# Schematic1_0.net
KiCad netlist of a schematic drawn in EAGLE
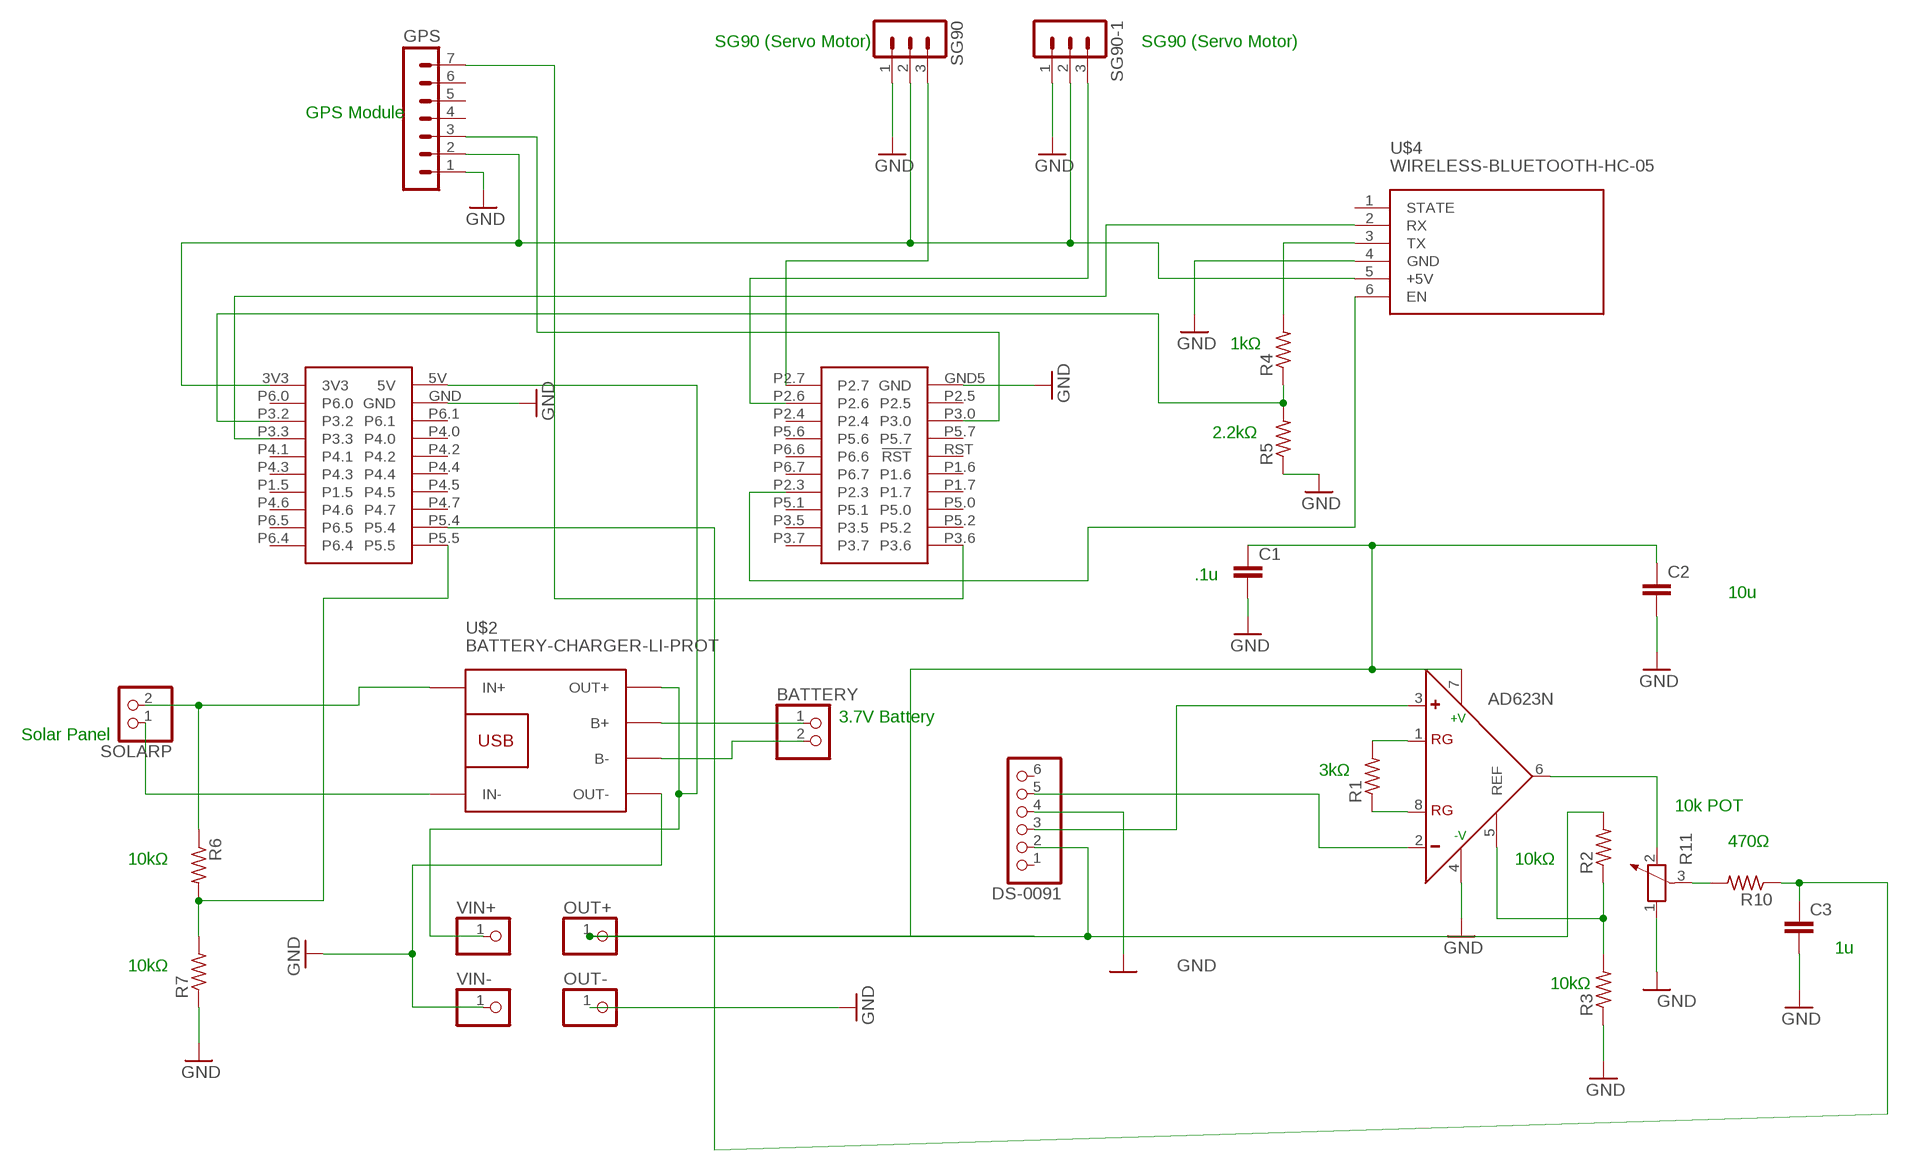
[diagram p0: schematic, sheet 1]

(export (version "E")
  (design (tool "Eeschema 10.0.6"))
  (components
    (comp (ref "BATTERY")
      (value "PINHD-1X2")
      (footprint "eagle-import:1X02")
      (libsource (lib "eagle-import") (part "PINHD-1X2"))
    )
    (comp (ref "C1")
      (value "C2,5-3")
      (footprint "eagle-import:C2.5-3")
      (libsource (lib "eagle-import") (part "C2,5-3"))
    )
    (comp (ref "C2")
      (value "C2,5-3")
      (footprint "eagle-import:C2.5-3")
      (libsource (lib "eagle-import") (part "C2,5-3"))
    )
    (comp (ref "C3")
      (value "C2,5-3")
      (footprint "eagle-import:C2.5-3")
      (libsource (lib "eagle-import") (part "C2,5-3"))
    )
    (comp (ref "DS-0091")
      (value "PINHD-1X6")
      (footprint "eagle-import:1X06")
      (libsource (lib "eagle-import") (part "PINHD-1X6"))
    )
    (comp (ref "GPS")
      (value "MA07-1")
      (footprint "eagle-import:MA07-1")
      (libsource (lib "eagle-import") (part "MA07-1"))
    )
    (comp (ref "IC1")
      (value "AD623N")
      (footprint "eagle-import:DIL08")
      (fields (field (name "MF") "ALTERA CORPORATION") (field (name "MPN") "AD623ANZ"))
      (libsource (lib "eagle-import") (part "AD623N"))
    )
    (comp (ref "OUT+")
      (value "PINHD-1X1")
      (footprint "eagle-import:1X01")
      (libsource (lib "eagle-import") (part "PINHD-1X1"))
    )
    (comp (ref "OUT-")
      (value "PINHD-1X1")
      (footprint "eagle-import:1X01")
      (libsource (lib "eagle-import") (part "PINHD-1X1"))
    )
    (comp (ref "R1")
      (value "R-US_0204/7")
      (footprint "eagle-import:0204_7")
      (libsource (lib "eagle-import") (part "R-US_0204/7"))
    )
    (comp (ref "R2")
      (value "R-US_0204/7")
      (footprint "eagle-import:0204_7")
      (libsource (lib "eagle-import") (part "R-US_0204/7"))
    )
    (comp (ref "R3")
      (value "R-US_0204/7")
      (footprint "eagle-import:0204_7")
      (libsource (lib "eagle-import") (part "R-US_0204/7"))
    )
    (comp (ref "R4")
      (value "R-US_0204/7")
      (footprint "eagle-import:0204_7")
      (libsource (lib "eagle-import") (part "R-US_0204/7"))
    )
    (comp (ref "R5")
      (value "R-US_0204/7")
      (footprint "eagle-import:0204_7")
      (libsource (lib "eagle-import") (part "R-US_0204/7"))
    )
    (comp (ref "R6")
      (value "R-US_0204/7")
      (footprint "eagle-import:0204_7")
      (libsource (lib "eagle-import") (part "R-US_0204/7"))
    )
    (comp (ref "R7")
      (value "R-US_0204/7")
      (footprint "eagle-import:0204_7")
      (libsource (lib "eagle-import") (part "R-US_0204/7"))
    )
    (comp (ref "R10")
      (value "R-US_0204/7")
      (footprint "eagle-import:0204_7")
      (libsource (lib "eagle-import") (part "R-US_0204/7"))
    )
    (comp (ref "R11")
      (value "POTENTIOMETER_PT-10")
      (footprint "eagle-import:PT-10")
      (libsource (lib "eagle-import") (part "POTENTIOMETER_PT-10"))
    )
    (comp (ref "SG90")
      (value "MA03-1")
      (footprint "eagle-import:MA03-1")
      (libsource (lib "eagle-import") (part "MA03-1"))
    )
    (comp (ref "SG90-1")
      (value "MA03-1")
      (footprint "eagle-import:MA03-1")
      (libsource (lib "eagle-import") (part "MA03-1"))
    )
    (comp (ref "SOLARP")
      (value "PINHD-1X2")
      (footprint "eagle-import:1X02")
      (libsource (lib "eagle-import") (part "PINHD-1X2"))
    )
    (comp (ref "U$1")
      (value "MSP432401R_40PIN")
      (footprint "eagle-import:MSP432P401R_40PIN")
      (libsource (lib "eagle-import") (part "MSP432401R_40PIN"))
    )
    (comp (ref "U$2")
      (value "BATTERY-CHARGER-LI-PROT")
      (footprint "eagle-import:BATTERY-CHARGER-LI-PROT")
      (libsource (lib "eagle-import") (part "BATTERY-CHARGER-LI-PROT"))
    )
    (comp (ref "U$4")
      (value "WIRELESS-BLUETOOTH-HC-05")
      (footprint "eagle-import:WIRELESS-BLUETOOTH-HC-05")
      (libsource (lib "eagle-import") (part "WIRELESS-BLUETOOTH-HC-05"))
    )
    (comp (ref "VIN+")
      (value "PINHD-1X1")
      (footprint "eagle-import:1X01")
      (libsource (lib "eagle-import") (part "PINHD-1X1"))
    )
    (comp (ref "VIN-")
      (value "PINHD-1X1")
      (footprint "eagle-import:1X01")
      (libsource (lib "eagle-import") (part "PINHD-1X1"))
    )
  )
  (nets
    (net (code "1") (name "GND") (class "Default")
      (node (ref "C1") (pin "2") (pinfunction "2_2") (pintype "passive"))
      (node (ref "C2") (pin "2") (pinfunction "2_2") (pintype "passive"))
      (node (ref "C3") (pin "2") (pinfunction "2_2") (pintype "passive"))
      (node (ref "DS-0091") (pin "4") (pinfunction "4_4") (pintype "passive"))
      (node (ref "GPS") (pin "1") (pinfunction "1_1") (pintype "passive"))
      (node (ref "IC1") (pin "4") (pinfunction "-V_4") (pintype "power_in"))
      (node (ref "OUT-") (pin "1") (pinfunction "1_1") (pintype "passive"))
      (node (ref "R11") (pin "1") (pinfunction "1_1") (pintype "passive"))
      (node (ref "R3") (pin "1") (pinfunction "1_1") (pintype "passive"))
      (node (ref "R5") (pin "1") (pinfunction "1_1") (pintype "passive"))
      (node (ref "R7") (pin "1") (pinfunction "1_1") (pintype "passive"))
      (node (ref "SG90") (pin "1") (pinfunction "1_1") (pintype "passive"))
      (node (ref "SG90-1") (pin "1") (pinfunction "1_1") (pintype "passive"))
      (node (ref "U$1") (pin "GND") (pinfunction "GND_GND") (pintype "bidirectional"))
      (node (ref "U$1") (pin "GND5") (pinfunction "GND_GND5") (pintype "bidirectional"))
      (node (ref "U$2") (pin "OUT-") (pinfunction "OUT-_OUT-") (pintype "bidirectional"))
      (node (ref "U$4") (pin "4") (pinfunction "GND_4") (pintype "power_in"))
      (node (ref "VIN-") (pin "1") (pinfunction "1_1") (pintype "passive"))
    )
    (net (code "2") (name "Net-(BATTERY-Pad1)") (class "Default")
      (node (ref "BATTERY") (pin "1") (pinfunction "1_1") (pintype "passive"))
      (node (ref "U$2") (pin "B+") (pinfunction "B+_B+") (pintype "bidirectional"))
    )
    (net (code "3") (name "Net-(BATTERY-Pad2)") (class "Default")
      (node (ref "BATTERY") (pin "2") (pinfunction "2_2") (pintype "passive"))
      (node (ref "U$2") (pin "B-") (pinfunction "B-_B-") (pintype "bidirectional"))
    )
    (net (code "4") (name "Net-(C3-Pad1)") (class "Default")
      (node (ref "C3") (pin "1") (pinfunction "1_1") (pintype "passive"))
      (node (ref "R10") (pin "1") (pinfunction "1_1") (pintype "passive"))
      (node (ref "U$1") (pin "P5.4") (pinfunction "P5.4_P5.4") (pintype "bidirectional"))
    )
    (net (code "5") (name "Net-(GPS-Pad3)") (class "Default")
      (node (ref "GPS") (pin "3") (pinfunction "3_3") (pintype "passive"))
      (node (ref "U$1") (pin "P3.0") (pinfunction "P3.0_P3.0") (pintype "bidirectional"))
    )
    (net (code "6") (name "Net-(GPS-Pad7)") (class "Default")
      (node (ref "GPS") (pin "7") (pinfunction "7_7") (pintype "passive"))
      (node (ref "U$1") (pin "P3.6") (pinfunction "P3.6_P3.6") (pintype "bidirectional"))
    )
    (net (code "7") (name "Net-(IC1-+)") (class "Default")
      (node (ref "DS-0091") (pin "3") (pinfunction "3_3") (pintype "passive"))
      (node (ref "IC1") (pin "3") (pinfunction "+_3") (pintype "input"))
    )
    (net (code "8") (name "Net-(IC1-+V)") (class "Default")
      (node (ref "C1") (pin "1") (pinfunction "1_1") (pintype "passive"))
      (node (ref "C2") (pin "1") (pinfunction "1_1") (pintype "passive"))
      (node (ref "DS-0091") (pin "2") (pinfunction "2_2") (pintype "passive"))
      (node (ref "IC1") (pin "7") (pinfunction "+V_7") (pintype "power_in"))
      (node (ref "OUT+") (pin "1") (pinfunction "1_1") (pintype "passive"))
      (node (ref "R2") (pin "2") (pinfunction "2_2") (pintype "passive"))
    )
    (net (code "9") (name "Net-(IC1--)") (class "Default")
      (node (ref "DS-0091") (pin "5") (pinfunction "5_5") (pintype "passive"))
      (node (ref "IC1") (pin "2") (pinfunction "-_2") (pintype "input"))
    )
    (net (code "10") (name "Net-(IC1-OUT)") (class "Default")
      (node (ref "IC1") (pin "6") (pinfunction "OUT_6") (pintype "output"))
      (node (ref "R11") (pin "2") (pinfunction "2_2") (pintype "passive"))
    )
    (net (code "11") (name "Net-(IC1-REF)") (class "Default")
      (node (ref "IC1") (pin "5") (pinfunction "REF_5") (pintype "passive"))
      (node (ref "R2") (pin "1") (pinfunction "1_1") (pintype "passive"))
      (node (ref "R3") (pin "2") (pinfunction "2_2") (pintype "passive"))
    )
    (net (code "12") (name "Net-(IC1-RG-Pad1)") (class "Default")
      (node (ref "IC1") (pin "1") (pinfunction "RG_1") (pintype "passive"))
      (node (ref "R1") (pin "2") (pinfunction "2_2") (pintype "passive"))
    )
    (net (code "13") (name "Net-(IC1-RG-Pad8)") (class "Default")
      (node (ref "IC1") (pin "8") (pinfunction "RG_8") (pintype "passive"))
      (node (ref "R1") (pin "1") (pinfunction "1_1") (pintype "passive"))
    )
    (net (code "14") (name "Net-(R4-Pad1)") (class "Default")
      (node (ref "R4") (pin "1") (pinfunction "1_1") (pintype "passive"))
      (node (ref "R5") (pin "2") (pinfunction "2_2") (pintype "passive"))
      (node (ref "U$1") (pin "P3.2") (pinfunction "P3.2_P3.2") (pintype "bidirectional"))
    )
    (net (code "15") (name "Net-(R6-Pad1)") (class "Default")
      (node (ref "R6") (pin "1") (pinfunction "1_1") (pintype "passive"))
      (node (ref "SOLARP") (pin "2") (pinfunction "2_2") (pintype "passive"))
      (node (ref "U$2") (pin "IN+") (pinfunction "IN+_IN+") (pintype "bidirectional"))
    )
    (net (code "16") (name "Net-(R6-Pad2)") (class "Default")
      (node (ref "R6") (pin "2") (pinfunction "2_2") (pintype "passive"))
      (node (ref "R7") (pin "2") (pinfunction "2_2") (pintype "passive"))
      (node (ref "U$1") (pin "P5.5") (pinfunction "P5.5_P5.5") (pintype "bidirectional"))
    )
    (net (code "17") (name "Net-(R10-Pad2)") (class "Default")
      (node (ref "R10") (pin "2") (pinfunction "2_2") (pintype "passive"))
      (node (ref "R11") (pin "3") (pinfunction "3_3") (pintype "passive"))
    )
    (net (code "18") (name "Net-(SG90-1-Pad3)") (class "Default")
      (node (ref "SG90-1") (pin "3") (pinfunction "3_3") (pintype "passive"))
      (node (ref "U$1") (pin "P2.6") (pinfunction "P2.6_P2.6") (pintype "bidirectional"))
    )
    (net (code "19") (name "Net-(SG90-Pad3)") (class "Default")
      (node (ref "SG90") (pin "3") (pinfunction "3_3") (pintype "passive"))
      (node (ref "U$1") (pin "P2.7") (pinfunction "P2.7_P2.7") (pintype "bidirectional"))
    )
    (net (code "20") (name "Net-(SOLARP-Pad1)") (class "Default")
      (node (ref "SOLARP") (pin "1") (pinfunction "1_1") (pintype "passive"))
      (node (ref "U$2") (pin "IN-") (pinfunction "IN-_IN-") (pintype "bidirectional"))
    )
    (net (code "21") (name "Net-(U$1-Pad5V)") (class "Default")
      (node (ref "U$1") (pin "5V") (pinfunction "5V_5V") (pintype "bidirectional"))
      (node (ref "U$2") (pin "OUT+") (pinfunction "OUT+_OUT+") (pintype "bidirectional"))
      (node (ref "VIN+") (pin "1") (pinfunction "1_1") (pintype "passive"))
    )
    (net (code "22") (name "Net-(U$4-+5V)") (class "Default")
      (node (ref "GPS") (pin "2") (pinfunction "2_2") (pintype "passive"))
      (node (ref "SG90") (pin "2") (pinfunction "2_2") (pintype "passive"))
      (node (ref "SG90-1") (pin "2") (pinfunction "2_2") (pintype "passive"))
      (node (ref "U$1") (pin "3V3") (pinfunction "3V3_3V3") (pintype "bidirectional"))
      (node (ref "U$4") (pin "5") (pinfunction "+5V_5") (pintype "power_in"))
    )
    (net (code "23") (name "Net-(U$4-EN)") (class "Default")
      (node (ref "U$1") (pin "P2.3") (pinfunction "P2.3_P2.3") (pintype "bidirectional"))
      (node (ref "U$4") (pin "6") (pinfunction "EN_6") (pintype "bidirectional"))
    )
    (net (code "24") (name "Net-(U$4-RX)") (class "Default")
      (node (ref "U$1") (pin "P3.3") (pinfunction "P3.3_P3.3") (pintype "bidirectional"))
      (node (ref "U$4") (pin "2") (pinfunction "RX_2") (pintype "bidirectional"))
    )
    (net (code "25") (name "Net-(U$4-TX)") (class "Default")
      (node (ref "R4") (pin "2") (pinfunction "2_2") (pintype "passive"))
      (node (ref "U$4") (pin "3") (pinfunction "TX_3") (pintype "bidirectional"))
    )
    (net (code "26") (name "unconnected-(DS-0091-Pad1)") (class "Default")
      (node (ref "DS-0091") (pin "1") (pinfunction "1_1") (pintype "passive"))
    )
    (net (code "27") (name "unconnected-(DS-0091-Pad6)") (class "Default")
      (node (ref "DS-0091") (pin "6") (pinfunction "6_6") (pintype "passive"))
    )
    (net (code "28") (name "unconnected-(GPS-Pad4)") (class "Default")
      (node (ref "GPS") (pin "4") (pinfunction "4_4") (pintype "passive"))
    )
    (net (code "29") (name "unconnected-(GPS-Pad5)") (class "Default")
      (node (ref "GPS") (pin "5") (pinfunction "5_5") (pintype "passive"))
    )
    (net (code "30") (name "unconnected-(GPS-Pad6)") (class "Default")
      (node (ref "GPS") (pin "6") (pinfunction "6_6") (pintype "passive"))
    )
    (net (code "31") (name "unconnected-(U$1-PadP1.5)") (class "Default")
      (node (ref "U$1") (pin "P1.5") (pinfunction "P1.5_P1.5") (pintype "bidirectional"))
    )
    (net (code "32") (name "unconnected-(U$1-PadP1.6)") (class "Default")
      (node (ref "U$1") (pin "P1.6") (pinfunction "P1.6_P1.6") (pintype "bidirectional"))
    )
    (net (code "33") (name "unconnected-(U$1-PadP1.7)") (class "Default")
      (node (ref "U$1") (pin "P1.7") (pinfunction "P1.7_P1.7") (pintype "bidirectional"))
    )
    (net (code "34") (name "unconnected-(U$1-PadP2.4)") (class "Default")
      (node (ref "U$1") (pin "P2.4") (pinfunction "P2.4_P2.4") (pintype "bidirectional"))
    )
    (net (code "35") (name "unconnected-(U$1-PadP2.5)") (class "Default")
      (node (ref "U$1") (pin "P2.5") (pinfunction "P2.5_P2.5") (pintype "bidirectional"))
    )
    (net (code "36") (name "unconnected-(U$1-PadP3.5)") (class "Default")
      (node (ref "U$1") (pin "P3.5") (pinfunction "P3.5_P3.5") (pintype "bidirectional"))
    )
    (net (code "37") (name "unconnected-(U$1-PadP3.7)") (class "Default")
      (node (ref "U$1") (pin "P3.7") (pinfunction "P3.7_P3.7") (pintype "bidirectional"))
    )
    (net (code "38") (name "unconnected-(U$1-PadP4.0)") (class "Default")
      (node (ref "U$1") (pin "P4.0") (pinfunction "P4.0_P4.0") (pintype "bidirectional"))
    )
    (net (code "39") (name "unconnected-(U$1-PadP4.1)") (class "Default")
      (node (ref "U$1") (pin "P4.1") (pinfunction "P4.1_P4.1") (pintype "bidirectional"))
    )
    (net (code "40") (name "unconnected-(U$1-PadP4.2)") (class "Default")
      (node (ref "U$1") (pin "P4.2") (pinfunction "P4.2_P4.2") (pintype "bidirectional"))
    )
    (net (code "41") (name "unconnected-(U$1-PadP4.3)") (class "Default")
      (node (ref "U$1") (pin "P4.3") (pinfunction "P4.3_P4.3") (pintype "bidirectional"))
    )
    (net (code "42") (name "unconnected-(U$1-PadP4.4)") (class "Default")
      (node (ref "U$1") (pin "P4.4") (pinfunction "P4.4_P4.4") (pintype "bidirectional"))
    )
    (net (code "43") (name "unconnected-(U$1-PadP4.5)") (class "Default")
      (node (ref "U$1") (pin "P4.5") (pinfunction "P4.5_P4.5") (pintype "bidirectional"))
    )
    (net (code "44") (name "unconnected-(U$1-PadP4.6)") (class "Default")
      (node (ref "U$1") (pin "P4.6") (pinfunction "P4.6_P4.6") (pintype "bidirectional"))
    )
    (net (code "45") (name "unconnected-(U$1-PadP4.7)") (class "Default")
      (node (ref "U$1") (pin "P4.7") (pinfunction "P4.7_P4.7") (pintype "bidirectional"))
    )
    (net (code "46") (name "unconnected-(U$1-PadP5.0)") (class "Default")
      (node (ref "U$1") (pin "P5.0") (pinfunction "P5.0_P5.0") (pintype "bidirectional"))
    )
    (net (code "47") (name "unconnected-(U$1-PadP5.1)") (class "Default")
      (node (ref "U$1") (pin "P5.1") (pinfunction "P5.1_P5.1") (pintype "bidirectional"))
    )
    (net (code "48") (name "unconnected-(U$1-PadP5.2)") (class "Default")
      (node (ref "U$1") (pin "P5.2") (pinfunction "P5.2_P5.2") (pintype "bidirectional"))
    )
    (net (code "49") (name "unconnected-(U$1-PadP5.6)") (class "Default")
      (node (ref "U$1") (pin "P5.6") (pinfunction "P5.6_P5.6") (pintype "bidirectional"))
    )
    (net (code "50") (name "unconnected-(U$1-PadP5.7)") (class "Default")
      (node (ref "U$1") (pin "P5.7") (pinfunction "P5.7_P5.7") (pintype "bidirectional"))
    )
    (net (code "51") (name "unconnected-(U$1-PadP6.0)") (class "Default")
      (node (ref "U$1") (pin "P6.0") (pinfunction "P6.0_P6.0") (pintype "bidirectional"))
    )
    (net (code "52") (name "unconnected-(U$1-PadP6.1)") (class "Default")
      (node (ref "U$1") (pin "P6.1") (pinfunction "P6.1_P6.1") (pintype "bidirectional"))
    )
    (net (code "53") (name "unconnected-(U$1-PadP6.4)") (class "Default")
      (node (ref "U$1") (pin "P6.4") (pinfunction "P6.4_P6.4") (pintype "bidirectional"))
    )
    (net (code "54") (name "unconnected-(U$1-PadP6.5)") (class "Default")
      (node (ref "U$1") (pin "P6.5") (pinfunction "P6.5_P6.5") (pintype "bidirectional"))
    )
    (net (code "55") (name "unconnected-(U$1-PadP6.6)") (class "Default")
      (node (ref "U$1") (pin "P6.6") (pinfunction "P6.6_P6.6") (pintype "bidirectional"))
    )
    (net (code "56") (name "unconnected-(U$1-PadP6.7)") (class "Default")
      (node (ref "U$1") (pin "P6.7") (pinfunction "P6.7_P6.7") (pintype "bidirectional"))
    )
    (net (code "57") (name "unconnected-(U$1-~{RST}-PadRST)") (class "Default")
      (node (ref "U$1") (pin "RST") (pinfunction "~{RST}_RST") (pintype "bidirectional"))
    )
    (net (code "58") (name "unconnected-(U$4-STATE-Pad1)") (class "Default")
      (node (ref "U$4") (pin "1") (pinfunction "STATE_1") (pintype "bidirectional"))
    )
  )
)
